# HLK.net
KiCad netlist of a schematic drawn in Altium Designer
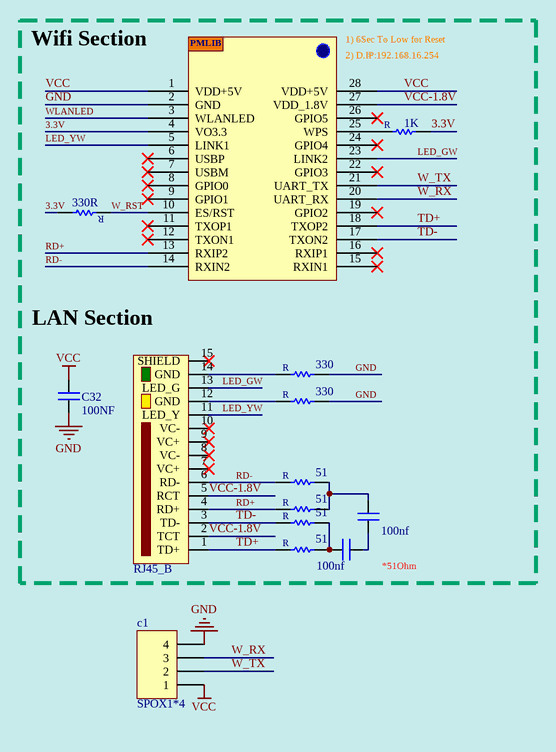
[diagram p0: HLK.SchDoc]

(export (version "E")
  (design (tool "Eeschema 10.0.6"))
  (components
    (comp (ref "3") (value "HLK_WifiModule") (libsource (lib "PMLIB") (part "HLK_WifiModule")))
    (comp (ref "34") (value "330") (footprint "R0805") (libsource (lib "PMLIB") (part "R0805")))
    (comp (ref "35") (value "330R") (footprint "R0805") (libsource (lib "PMLIB") (part "R0805")))
    (comp (ref "43") (value "330") (footprint "R0805") (libsource (lib "PMLIB") (part "R0805")))
    (comp (ref "89") (value "RJ45_B") (footprint "RJ45_B") (libsource (lib "PMLIB") (part "RJ45_B")))
    (comp (ref "c1") (value "SPOX1*4") (footprint "SPOX_1*4RIGHT") (libsource (lib "PMLIB") (part "SPOX1*4")))
    (comp (ref "C32")
      (value "100NF")
      (footprint "Cap0805")
      (description "surface mount capacitor (size 805)")
      (libsource (lib "PMLIB") (part "Cap0805"))
    )
    (comp (ref "C93")
      (value "100nf")
      (footprint "Cap0805")
      (description "surface mount capacitor (size 805)")
      (libsource (lib "PMLIB") (part "Cap0805"))
    )
    (comp (ref "C94")
      (value "100nf")
      (footprint "Cap0805")
      (description "surface mount capacitor (size 805)")
      (libsource (lib "PMLIB") (part "Cap0805"))
    )
    (comp (ref "PO") (value "51") (footprint "R0805") (libsource (lib "PMLIB") (part "R0805")))
    (comp (ref "POS") (value "51") (footprint "R0805") (libsource (lib "PMLIB") (part "R0805")))
    (comp (ref "POS2") (value "51") (footprint "R0805") (libsource (lib "PMLIB") (part "R0805")))
    (comp (ref "POS3") (value "51") (footprint "R0805") (libsource (lib "PMLIB") (part "R0805")))
    (comp (ref "POSWW") (value "1K") (footprint "R0805") (libsource (lib "PMLIB") (part "R0805")))
  )
  (nets
    (net (code "1") (name "/3.3V") (class "Default")
      (node (ref "3") (pin "4") (pinfunction "VO3.3_4") (pintype "passive"))
      (node (ref "35") (pin "1") (pinfunction "1_1") (pintype "passive"))
      (node (ref "POSWW") (pin "1") (pinfunction "1_1") (pintype "passive"))
    )
    (net (code "2") (name "/LED_GW") (class "Default")
      (node (ref "3") (pin "23") (pinfunction "LINK2_23") (pintype "passive"))
      (node (ref "89") (pin "13") (pinfunction "LED_G_13") (pintype "passive"))
    )
    (net (code "3") (name "/LED_YW") (class "Default")
      (node (ref "3") (pin "5") (pinfunction "LINK1_5") (pintype "passive"))
      (node (ref "89") (pin "11") (pinfunction "LED_Y_11") (pintype "passive"))
    )
    (net (code "4") (name "/RD+") (class "Default")
      (node (ref "3") (pin "13") (pinfunction "RXIP2_13") (pintype "passive"))
      (node (ref "89") (pin "4") (pinfunction "RD+_4") (pintype "passive"))
      (node (ref "POS3") (pin "2") (pinfunction "2_2") (pintype "passive"))
    )
    (net (code "5") (name "/RD-") (class "Default")
      (node (ref "3") (pin "14") (pinfunction "RXIN2_14") (pintype "passive"))
      (node (ref "89") (pin "6") (pinfunction "RD-_6") (pintype "passive"))
      (node (ref "POS2") (pin "2") (pinfunction "2_2") (pintype "passive"))
    )
    (net (code "6") (name "/TD+") (class "Default")
      (node (ref "3") (pin "18") (pinfunction "TXOP2_18") (pintype "passive"))
      (node (ref "89") (pin "1") (pinfunction "TD+_1") (pintype "passive"))
      (node (ref "PO") (pin "2") (pinfunction "2_2") (pintype "passive"))
    )
    (net (code "7") (name "/TD-") (class "Default")
      (node (ref "3") (pin "17") (pinfunction "TXON2_17") (pintype "passive"))
      (node (ref "89") (pin "3") (pinfunction "TD-_3") (pintype "passive"))
      (node (ref "POS") (pin "2") (pinfunction "2_2") (pintype "passive"))
    )
    (net (code "8") (name "/VCC-1.8V") (class "Default")
      (node (ref "3") (pin "27") (pinfunction "VDD_1.8V_27") (pintype "passive"))
      (node (ref "89") (pin "2") (pinfunction "TCT_2") (pintype "passive"))
      (node (ref "89") (pin "5") (pinfunction "RCT_5") (pintype "passive"))
    )
    (net (code "9") (name "/WLANLED") (class "Default")
      (node (ref "3") (pin "3") (pinfunction "WLANLED_3") (pintype "passive"))
    )
    (net (code "10") (name "/W_RST") (class "Default")
      (node (ref "3") (pin "10") (pinfunction "ES/RST_10") (pintype "passive"))
      (node (ref "35") (pin "2") (pinfunction "2_2") (pintype "passive"))
    )
    (net (code "11") (name "/W_RX") (class "Default")
      (node (ref "3") (pin "20") (pinfunction "UART_RX_20") (pintype "passive"))
      (node (ref "c1") (pin "3") (pinfunction "3_3") (pintype "passive"))
    )
    (net (code "12") (name "/W_TX") (class "Default")
      (node (ref "3") (pin "21") (pinfunction "UART_TX_21") (pintype "passive"))
      (node (ref "c1") (pin "2") (pinfunction "2_2") (pintype "passive"))
    )
    (net (code "13") (name "GND") (class "Default")
      (node (ref "3") (pin "2") (pinfunction "GND_2") (pintype "passive"))
      (node (ref "34") (pin "1") (pinfunction "1_1") (pintype "passive"))
      (node (ref "43") (pin "1") (pinfunction "1_1") (pintype "passive"))
      (node (ref "C32") (pin "1") (pinfunction "1_1") (pintype "passive"))
      (node (ref "c1") (pin "4") (pinfunction "4_4") (pintype "passive"))
    )
    (net (code "14") (name "Net-(3-WPS)") (class "Default")
      (node (ref "3") (pin "25") (pinfunction "WPS_25") (pintype "passive"))
      (node (ref "POSWW") (pin "2") (pinfunction "2_2") (pintype "passive"))
    )
    (net (code "15") (name "Net-(34-Pad2)") (class "Default")
      (node (ref "34") (pin "2") (pinfunction "2_2") (pintype "passive"))
      (node (ref "89") (pin "14") (pinfunction "GND_14") (pintype "passive"))
    )
    (net (code "16") (name "Net-(43-Pad2)") (class "Default")
      (node (ref "43") (pin "2") (pinfunction "2_2") (pintype "passive"))
      (node (ref "89") (pin "12") (pinfunction "GND_12") (pintype "passive"))
    )
    (net (code "17") (name "Net-(C93-Pad1)") (class "Default")
      (node (ref "C93") (pin "1") (pinfunction "1_1") (pintype "passive"))
      (node (ref "C94") (pin "1") (pinfunction "1_1") (pintype "passive"))
    )
    (net (code "18") (name "Net-(C93-Pad2)") (class "Default")
      (node (ref "C93") (pin "2") (pinfunction "2_2") (pintype "passive"))
      (node (ref "PO") (pin "1") (pinfunction "1_1") (pintype "passive"))
      (node (ref "POS") (pin "1") (pinfunction "1_1") (pintype "passive"))
    )
    (net (code "19") (name "Net-(C94-Pad2)") (class "Default")
      (node (ref "C94") (pin "2") (pinfunction "2_2") (pintype "passive"))
      (node (ref "POS2") (pin "1") (pinfunction "1_1") (pintype "passive"))
      (node (ref "POS3") (pin "1") (pinfunction "1_1") (pintype "passive"))
    )
    (net (code "20") (name "VCC") (class "Default")
      (node (ref "3") (pin "1") (pinfunction "VDD+5V_1") (pintype "passive"))
      (node (ref "3") (pin "28") (pinfunction "VDD+5V_28") (pintype "passive"))
      (node (ref "C32") (pin "2") (pinfunction "2_2") (pintype "passive"))
      (node (ref "c1") (pin "1") (pinfunction "1_1") (pintype "passive"))
    )
    (net (code "21") (name "unconnected-(3-GPIO0-Pad8)") (class "Default")
      (node (ref "3") (pin "8") (pinfunction "GPIO0_8") (pintype "passive+no_connect"))
    )
    (net (code "22") (name "unconnected-(3-GPIO1-Pad9)") (class "Default")
      (node (ref "3") (pin "9") (pinfunction "GPIO1_9") (pintype "passive+no_connect"))
    )
    (net (code "23") (name "unconnected-(3-GPIO2-Pad19)") (class "Default")
      (node (ref "3") (pin "19") (pinfunction "GPIO2_19") (pintype "passive+no_connect"))
    )
    (net (code "24") (name "unconnected-(3-GPIO3-Pad22)") (class "Default")
      (node (ref "3") (pin "22") (pinfunction "GPIO3_22") (pintype "passive+no_connect"))
    )
    (net (code "25") (name "unconnected-(3-GPIO4-Pad24)") (class "Default")
      (node (ref "3") (pin "24") (pinfunction "GPIO4_24") (pintype "passive+no_connect"))
    )
    (net (code "26") (name "unconnected-(3-GPIO5-Pad26)") (class "Default")
      (node (ref "3") (pin "26") (pinfunction "GPIO5_26") (pintype "passive+no_connect"))
    )
    (net (code "27") (name "unconnected-(3-RXIN1-Pad15)") (class "Default")
      (node (ref "3") (pin "15") (pinfunction "RXIN1_15") (pintype "passive+no_connect"))
    )
    (net (code "28") (name "unconnected-(3-RXIP1-Pad16)") (class "Default")
      (node (ref "3") (pin "16") (pinfunction "RXIP1_16") (pintype "passive+no_connect"))
    )
    (net (code "29") (name "unconnected-(3-TXON1-Pad12)") (class "Default")
      (node (ref "3") (pin "12") (pinfunction "TXON1_12") (pintype "passive+no_connect"))
    )
    (net (code "30") (name "unconnected-(3-TXOP1-Pad11)") (class "Default")
      (node (ref "3") (pin "11") (pinfunction "TXOP1_11") (pintype "passive+no_connect"))
    )
    (net (code "31") (name "unconnected-(3-USBM-Pad7)") (class "Default")
      (node (ref "3") (pin "7") (pinfunction "USBM_7") (pintype "passive+no_connect"))
    )
    (net (code "32") (name "unconnected-(3-USBP-Pad6)") (class "Default")
      (node (ref "3") (pin "6") (pinfunction "USBP_6") (pintype "passive+no_connect"))
    )
    (net (code "33") (name "unconnected-(89-SHIELD-Pad15)") (class "Default")
      (node (ref "89") (pin "15") (pinfunction "SHIELD_15") (pintype "passive+no_connect"))
    )
    (net (code "34") (name "unconnected-(89-VC+-Pad7)") (class "Default")
      (node (ref "89") (pin "7") (pinfunction "VC+_7") (pintype "passive+no_connect"))
    )
    (net (code "35") (name "unconnected-(89-VC+-Pad9)") (class "Default")
      (node (ref "89") (pin "9") (pinfunction "VC+_9") (pintype "passive+no_connect"))
    )
    (net (code "36") (name "unconnected-(89-VC--Pad8)") (class "Default")
      (node (ref "89") (pin "8") (pinfunction "VC-_8") (pintype "passive+no_connect"))
    )
    (net (code "37") (name "unconnected-(89-VC--Pad10)") (class "Default")
      (node (ref "89") (pin "10") (pinfunction "VC-_10") (pintype "passive+no_connect"))
    )
  )
)
